# lte.net
KiCad netlist of a schematic drawn in Altium Designer
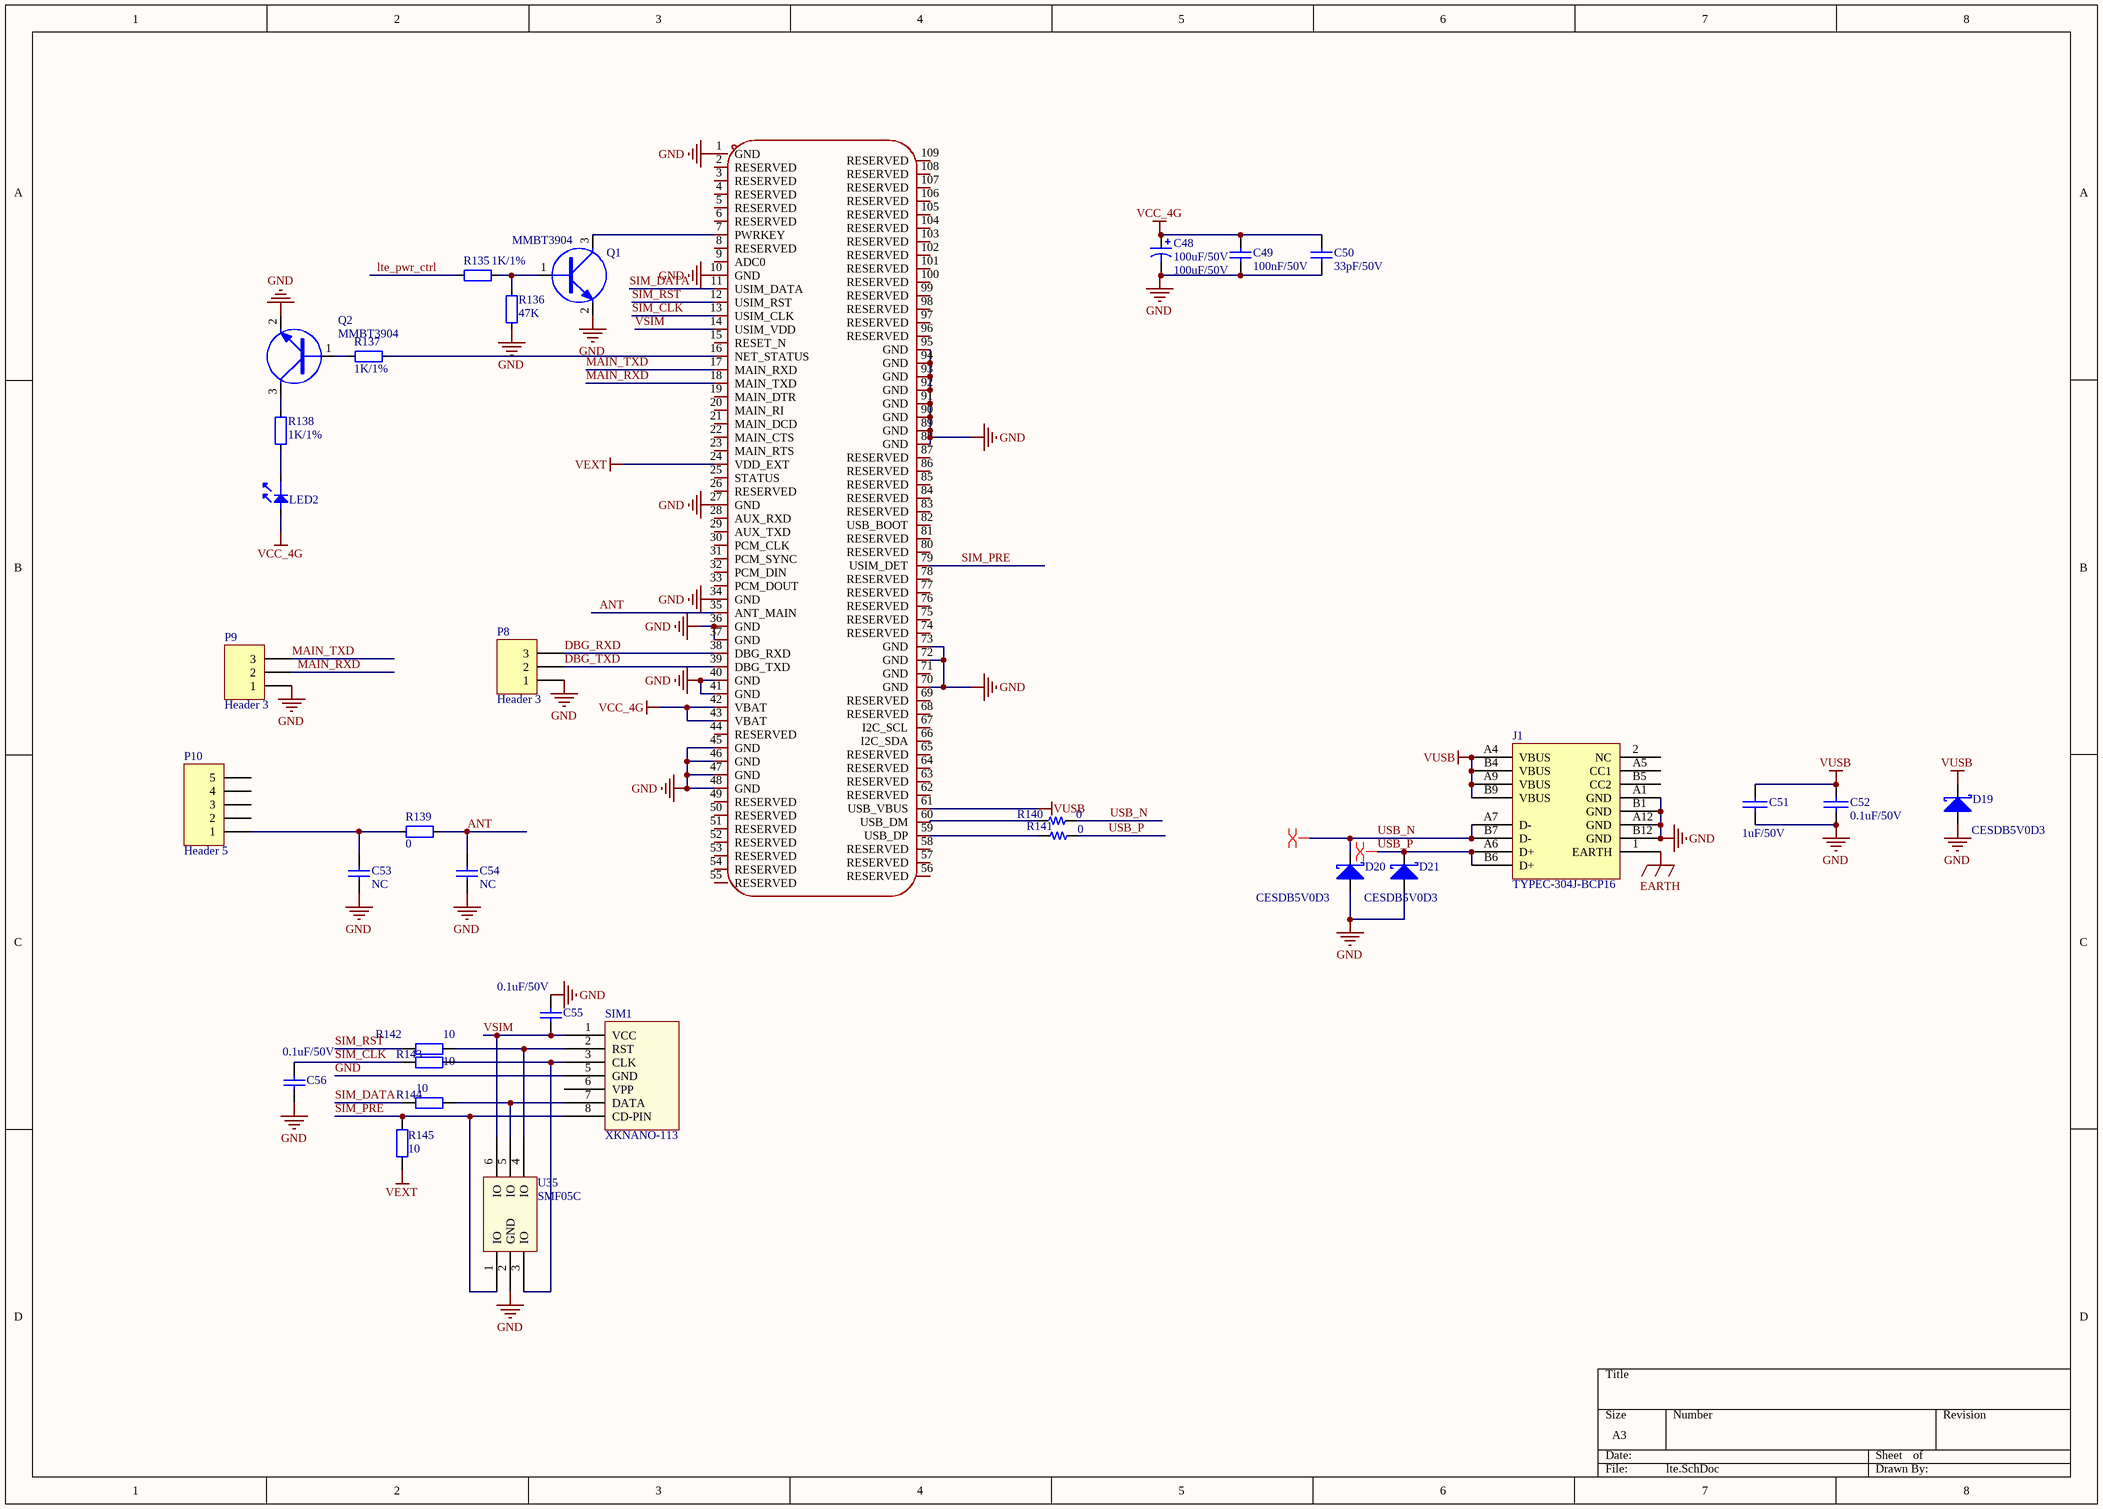
[diagram p0: lte.SchDoc]

(export (version "E")
  (design (tool "Eeschema 10.0.6"))
  (components
    (comp (ref "C48")
      (value "100uF/50V")
      (footprint "CAP-SMD_BD6.3-L6.5-W6.5-LS7.0-FD:CAP-SMD_BD6.3-L6.5-W6.5-LS7.0-FD")
      (description "Polarized Capacitor (Surface Mount)")
      (fields (field (name "ALTIUM_VALUE") "100uF/50V"))
      (libsource (lib "Miscellaneous Devices") (part "Cap Pol3"))
    )
    (comp (ref "C49")
      (value "100nF/50V")
      (footprint "0603C")
      (description "Capacitor")
      (libsource (lib "Miscellaneous Devices") (part "Cap"))
    )
    (comp (ref "C50")
      (value "33pF/50V")
      (footprint "0603C")
      (description "Capacitor")
      (libsource (lib "Miscellaneous Devices") (part "Cap"))
    )
    (comp (ref "C51")
      (value "1uF/50V")
      (footprint "CAPC1608X092N_0603")
      (fields (field (name "PARTNUMBER") "CL10A105KB8NNNC"))
      (libsource (lib "SM") (part "CAP"))
    )
    (comp (ref "C52")
      (value "0.1uF/50V")
      (footprint "CAPC1608X092N_0603")
      (fields (field (name "PARTNUMBER") "CC0603KRX7R9BB104"))
      (libsource (lib "SM") (part "CAP"))
    )
    (comp (ref "C53")
      (value "NC")
      (footprint "0603c")
      (description "Capacitor")
      (libsource (lib "Miscellaneous Devices") (part "Cap"))
    )
    (comp (ref "C54")
      (value "NC")
      (footprint "0603c")
      (description "Capacitor")
      (libsource (lib "Miscellaneous Devices") (part "Cap"))
    )
    (comp (ref "C55")
      (value "0.1uF/50V")
      (footprint "0603c")
      (description "Capacitor")
      (libsource (lib "Miscellaneous Devices") (part "Cap"))
    )
    (comp (ref "C56")
      (value "0.1uF/50V")
      (footprint "0603c")
      (description "Capacitor")
      (libsource (lib "Miscellaneous Devices") (part "Cap"))
    )
    (comp (ref "D19") (value "CESDB5V0D3") (footprint "SOD323") (libsource (lib "*") (part "DIODE S")))
    (comp (ref "D20") (value "CESDB5V0D3") (footprint "SOD323") (libsource (lib "*") (part "DIODE S")))
    (comp (ref "D21") (value "CESDB5V0D3") (footprint "SOD323") (libsource (lib "*") (part "DIODE S")))
    (comp (ref "J1")
      (value "TYPEC-304J-BCP16")
      (footprint "TYPEC_16P")
      (libsource (lib "Schlib_20110825") (part "TYPE C_16P"))
    )
    (comp (ref "LED2")
      (value "LED_Green_19-217")
      (footprint "0603led")
      (libsource (lib "RC_M_D_00") (part "LED_Green_19-217"))
    )
    (comp (ref "P8")
      (value "Header 3")
      (footprint "HDR1X3")
      (description "Header, 3-Pin")
      (libsource (lib "Miscellaneous Connectors") (part "Header 3"))
    )
    (comp (ref "P9")
      (value "Header 3")
      (footprint "HDR1X3")
      (description "Header, 3-Pin")
      (libsource (lib "Miscellaneous Connectors") (part "Header 3"))
    )
    (comp (ref "P10")
      (value "Header 5")
      (footprint "controller_V1.3.1:KH-SMA-KE-Z")
      (description "Header, 5-Pin")
      (libsource (lib "Miscellaneous Connectors") (part "Header 5"))
    )
    (comp (ref "Q1")
      (value "MMBT3904")
      (footprint "SOT23-3")
      (libsource (lib "CenLib") (part "NPN_MMBT3904"))
    )
    (comp (ref "Q2")
      (value "MMBT3904")
      (footprint "SOT23-3")
      (libsource (lib "CenLib") (part "NPN_MMBT3904"))
    )
    (comp (ref "R135") (value "1K/1%") (footprint "0603R") (libsource (lib "RC_M_D_00") (part "RES0603")))
    (comp (ref "R136") (value "47K") (footprint "0603r") (libsource (lib "RC_M_D_00") (part "RES0603")))
    (comp (ref "R137") (value "1K/1%") (footprint "0603r") (libsource (lib "RC_M_D_00") (part "RES0603")))
    (comp (ref "R138") (value "1K/1%") (footprint "0603R") (libsource (lib "RC_M_D_00") (part "RES0603")))
    (comp (ref "R139") (value "0") (footprint "0603r") (libsource (lib "RC_M_D_00") (part "RES0603")))
    (comp (ref "R140")
      (value "0")
      (footprint "RESC1608X055N_0603")
      (fields (field (name "PARTNUMBER") "RC0603FR-071KL"))
      (libsource (lib "JRJ_1") (part "R"))
    )
    (comp (ref "R141")
      (value "0")
      (footprint "RESC1608X055N_0603")
      (fields (field (name "PARTNUMBER") "RC0603FR-071KL"))
      (libsource (lib "JRJ_1") (part "R"))
    )
    (comp (ref "R142")
      (value "10")
      (footprint "0603r")
      (description "Resistor")
      (libsource (lib "Miscellaneous Devices") (part "Res2"))
    )
    (comp (ref "R143")
      (value "10")
      (footprint "0603r")
      (description "Resistor")
      (libsource (lib "Miscellaneous Devices") (part "Res2"))
    )
    (comp (ref "R144")
      (value "10")
      (footprint "0603r")
      (description "Resistor")
      (libsource (lib "Miscellaneous Devices") (part "Res2"))
    )
    (comp (ref "R145")
      (value "10")
      (footprint "0603r")
      (description "Resistor")
      (libsource (lib "") (part "Res2_1"))
    )
    (comp (ref "SIM1") (value "XKNANO-113") (footprint "Nano SIM") (libsource (lib "lm") (part "nano sim")))
    (comp (ref "U34")
      (value "EC800ECNNQ-N03-SNNSA")
      (footprint "LCC-LGA-109_L17.7-W15.8-P1.10_MC661:LCC-LGA-109_L17.7-W15.8-P1.10_MC661")
      (libsource (lib "altium-import") (part "root_0_EC800ECNNQ-N03-SNNSA_"))
    )
    (comp (ref "U35") (value "SMF05C") (footprint "sc70-6l") (libsource (lib "lm") (part "SMF05C")))
  )
  (nets
    (net (code "1") (name "/ANT") (class "Default")
      (node (ref "C54") (pin "1") (pinfunction "1_1") (pintype "passive"))
      (node (ref "R139") (pin "1") (pinfunction "1_1") (pintype "passive"))
      (node (ref "U34") (pin "35") (pinfunction "ANT_MAIN_35") (pintype "passive"))
    )
    (net (code "2") (name "/DBG_RXD") (class "Default")
      (node (ref "P8") (pin "3") (pinfunction "3_3") (pintype "passive"))
      (node (ref "U34") (pin "38") (pinfunction "DBG_RXD_38") (pintype "passive"))
    )
    (net (code "3") (name "/DBG_TXD") (class "Default")
      (node (ref "P8") (pin "2") (pinfunction "2_2") (pintype "passive"))
      (node (ref "U34") (pin "39") (pinfunction "DBG_TXD_39") (pintype "passive"))
    )
    (net (code "4") (name "/MAIN_RXD") (class "Default")
      (node (ref "P9") (pin "2") (pinfunction "2_2") (pintype "passive"))
      (node (ref "U34") (pin "18") (pinfunction "MAIN_TXD_18") (pintype "passive"))
    )
    (net (code "5") (name "/MAIN_TXD") (class "Default")
      (node (ref "P9") (pin "3") (pinfunction "3_3") (pintype "passive"))
      (node (ref "U34") (pin "17") (pinfunction "MAIN_RXD_17") (pintype "passive"))
    )
    (net (code "6") (name "/SIM_CLK") (class "Default")
      (node (ref "C56") (pin "1") (pinfunction "1_1") (pintype "passive"))
      (node (ref "R143") (pin "2") (pinfunction "2_2") (pintype "passive"))
      (node (ref "U34") (pin "13") (pinfunction "USIM_CLK_13") (pintype "passive"))
    )
    (net (code "7") (name "/SIM_DATA") (class "Default")
      (node (ref "R144") (pin "2") (pinfunction "2_2") (pintype "passive"))
      (node (ref "U34") (pin "11") (pinfunction "USIM_DATA_11") (pintype "passive"))
    )
    (net (code "8") (name "/SIM_PRE") (class "Default")
      (node (ref "R145") (pin "1") (pinfunction "1_1") (pintype "passive"))
      (node (ref "SIM1") (pin "8") (pinfunction "CD-PIN_8") (pintype "passive"))
      (node (ref "U34") (pin "79") (pinfunction "USIM_DET_79") (pintype "passive"))
      (node (ref "U35") (pin "1") (pinfunction "IO_1") (pintype "passive"))
    )
    (net (code "9") (name "/SIM_RST") (class "Default")
      (node (ref "R142") (pin "2") (pinfunction "2_2") (pintype "passive"))
      (node (ref "U34") (pin "12") (pinfunction "USIM_RST_12") (pintype "passive"))
    )
    (net (code "10") (name "/USB_N") (class "Default")
      (node (ref "D20") (pin "2") (pinfunction "K_2") (pintype "passive"))
      (node (ref "J1") (pin "A7") (pinfunction "D-_A7") (pintype "passive"))
      (node (ref "J1") (pin "B7") (pinfunction "D-_B7") (pintype "passive"))
      (node (ref "R140") (pin "1") (pintype "passive"))
    )
    (net (code "11") (name "/USB_P") (class "Default")
      (node (ref "D21") (pin "2") (pinfunction "K_2") (pintype "passive"))
      (node (ref "J1") (pin "A6") (pinfunction "D+_A6") (pintype "passive"))
      (node (ref "J1") (pin "B6") (pinfunction "D+_B6") (pintype "passive"))
      (node (ref "R141") (pin "1") (pintype "passive"))
    )
    (net (code "12") (name "/VSIM") (class "Default")
      (node (ref "C55") (pin "2") (pinfunction "2_2") (pintype "passive"))
      (node (ref "SIM1") (pin "1") (pinfunction "VCC_1") (pintype "passive"))
      (node (ref "U34") (pin "14") (pinfunction "USIM_VDD_14") (pintype "passive"))
      (node (ref "U35") (pin "6") (pinfunction "IO_6") (pintype "passive"))
    )
    (net (code "13") (name "/lte_pwr_ctrl") (class "Default")
      (node (ref "R135") (pin "1") (pinfunction "1_1") (pintype "passive"))
    )
    (net (code "14") (name "EARTH") (class "Default")
      (node (ref "J1") (pin "1") (pinfunction "EARTH_1") (pintype "passive"))
    )
    (net (code "15") (name "GND") (class "Default")
      (node (ref "C48") (pin "2") (pinfunction "2_2") (pintype "passive"))
      (node (ref "C49") (pin "1") (pinfunction "1_1") (pintype "passive"))
      (node (ref "C50") (pin "1") (pinfunction "1_1") (pintype "passive"))
      (node (ref "C51") (pin "1") (pinfunction "1_1") (pintype "passive"))
      (node (ref "C52") (pin "1") (pinfunction "1_1") (pintype "passive"))
      (node (ref "C53") (pin "2") (pinfunction "2_2") (pintype "passive"))
      (node (ref "C54") (pin "2") (pinfunction "2_2") (pintype "passive"))
      (node (ref "C55") (pin "1") (pinfunction "1_1") (pintype "passive"))
      (node (ref "C56") (pin "2") (pinfunction "2_2") (pintype "passive"))
      (node (ref "D19") (pin "1") (pinfunction "A_1") (pintype "passive"))
      (node (ref "D20") (pin "1") (pinfunction "A_1") (pintype "passive"))
      (node (ref "D21") (pin "1") (pinfunction "A_1") (pintype "passive"))
      (node (ref "J1") (pin "A1") (pinfunction "GND_A1") (pintype "passive"))
      (node (ref "J1") (pin "A12") (pinfunction "GND_A12") (pintype "passive"))
      (node (ref "J1") (pin "B1") (pinfunction "GND_B1") (pintype "passive"))
      (node (ref "J1") (pin "B12") (pinfunction "GND_B12") (pintype "passive"))
      (node (ref "P8") (pin "1") (pinfunction "1_1") (pintype "passive"))
      (node (ref "P9") (pin "1") (pinfunction "1_1") (pintype "passive"))
      (node (ref "Q1") (pin "2") (pinfunction "E_2") (pintype "passive"))
      (node (ref "Q2") (pin "2") (pinfunction "E_2") (pintype "passive"))
      (node (ref "R136") (pin "1") (pinfunction "1_1") (pintype "passive"))
      (node (ref "SIM1") (pin "5") (pinfunction "GND_5") (pintype "passive"))
      (node (ref "U34") (pin "1") (pinfunction "GND_1") (pintype "passive"))
      (node (ref "U34") (pin "10") (pinfunction "GND_10") (pintype "passive"))
      (node (ref "U34") (pin "27") (pinfunction "GND_27") (pintype "passive"))
      (node (ref "U34") (pin "34") (pinfunction "GND_34") (pintype "passive"))
      (node (ref "U34") (pin "36") (pinfunction "GND_36") (pintype "passive"))
      (node (ref "U34") (pin "37") (pinfunction "GND_37") (pintype "passive"))
      (node (ref "U34") (pin "40") (pinfunction "GND_40") (pintype "passive"))
      (node (ref "U34") (pin "41") (pinfunction "GND_41") (pintype "passive"))
      (node (ref "U34") (pin "45") (pinfunction "GND_45") (pintype "passive"))
      (node (ref "U34") (pin "46") (pinfunction "GND_46") (pintype "passive"))
      (node (ref "U34") (pin "47") (pinfunction "GND_47") (pintype "passive"))
      (node (ref "U34") (pin "48") (pinfunction "GND_48") (pintype "passive"))
      (node (ref "U34") (pin "70") (pinfunction "GND_70") (pintype "passive"))
      (node (ref "U34") (pin "72") (pinfunction "GND_72") (pintype "passive"))
      (node (ref "U34") (pin "73") (pinfunction "GND_73") (pintype "passive"))
      (node (ref "U34") (pin "88") (pinfunction "GND_88") (pintype "passive"))
      (node (ref "U34") (pin "89") (pinfunction "GND_89") (pintype "passive"))
      (node (ref "U34") (pin "90") (pinfunction "GND_90") (pintype "passive"))
      (node (ref "U34") (pin "91") (pinfunction "GND_91") (pintype "passive"))
      (node (ref "U34") (pin "92") (pinfunction "GND_92") (pintype "passive"))
      (node (ref "U34") (pin "93") (pinfunction "GND_93") (pintype "passive"))
      (node (ref "U34") (pin "94") (pinfunction "GND_94") (pintype "passive"))
      (node (ref "U34") (pin "95") (pinfunction "GND_95") (pintype "passive"))
      (node (ref "U35") (pin "2") (pinfunction "GND_2") (pintype "passive"))
    )
    (net (code "16") (name "Net-(C53-Pad1)") (class "Default")
      (node (ref "C53") (pin "1") (pinfunction "1_1") (pintype "passive"))
      (node (ref "P10") (pin "1") (pinfunction "1_1") (pintype "passive"))
      (node (ref "R139") (pin "2") (pinfunction "2_2") (pintype "passive"))
    )
    (net (code "17") (name "Net-(LED2-Pad2)") (class "Default")
      (node (ref "LED2") (pin "2") (pinfunction "2_2") (pintype "passive"))
      (node (ref "R138") (pin "1") (pinfunction "1_1") (pintype "passive"))
    )
    (net (code "18") (name "Net-(Q1-B)") (class "Default")
      (node (ref "Q1") (pin "1") (pinfunction "B_1") (pintype "passive"))
      (node (ref "R135") (pin "2") (pinfunction "2_2") (pintype "passive"))
      (node (ref "R136") (pin "2") (pinfunction "2_2") (pintype "passive"))
    )
    (net (code "19") (name "Net-(Q1-C)") (class "Default")
      (node (ref "Q1") (pin "3") (pinfunction "C_3") (pintype "passive"))
      (node (ref "U34") (pin "7") (pinfunction "PWRKEY_7") (pintype "passive"))
    )
    (net (code "20") (name "Net-(Q2-B)") (class "Default")
      (node (ref "Q2") (pin "1") (pinfunction "B_1") (pintype "passive"))
      (node (ref "R137") (pin "2") (pinfunction "2_2") (pintype "passive"))
    )
    (net (code "21") (name "Net-(Q2-C)") (class "Default")
      (node (ref "Q2") (pin "3") (pinfunction "C_3") (pintype "passive"))
      (node (ref "R138") (pin "2") (pinfunction "2_2") (pintype "passive"))
    )
    (net (code "22") (name "Net-(SIM1-CLK)") (class "Default")
      (node (ref "R143") (pin "1") (pinfunction "1_1") (pintype "passive"))
      (node (ref "SIM1") (pin "3") (pinfunction "CLK_3") (pintype "passive"))
      (node (ref "U35") (pin "3") (pinfunction "IO_3") (pintype "passive"))
    )
    (net (code "23") (name "Net-(SIM1-DATA)") (class "Default")
      (node (ref "R144") (pin "1") (pinfunction "1_1") (pintype "passive"))
      (node (ref "SIM1") (pin "7") (pinfunction "DATA_7") (pintype "passive"))
      (node (ref "U35") (pin "5") (pinfunction "IO_5") (pintype "passive"))
    )
    (net (code "24") (name "Net-(SIM1-RST)") (class "Default")
      (node (ref "R142") (pin "1") (pinfunction "1_1") (pintype "passive"))
      (node (ref "SIM1") (pin "2") (pinfunction "RST_2") (pintype "passive"))
      (node (ref "U35") (pin "4") (pinfunction "IO_4") (pintype "passive"))
    )
    (net (code "25") (name "Net-(U34-NET_STATUS)") (class "Default")
      (node (ref "R137") (pin "1") (pinfunction "1_1") (pintype "passive"))
      (node (ref "U34") (pin "16") (pinfunction "NET_STATUS_16") (pintype "passive"))
    )
    (net (code "26") (name "Net-(U34-USB_DM)") (class "Default")
      (node (ref "R140") (pin "2") (pintype "passive"))
      (node (ref "U34") (pin "60") (pinfunction "USB_DM_60") (pintype "passive"))
    )
    (net (code "27") (name "Net-(U34-USB_DP)") (class "Default")
      (node (ref "R141") (pin "2") (pintype "passive"))
      (node (ref "U34") (pin "59") (pinfunction "USB_DP_59") (pintype "passive"))
    )
    (net (code "28") (name "VCC_4G") (class "Default")
      (node (ref "C48") (pin "1") (pinfunction "1_1") (pintype "passive"))
      (node (ref "C49") (pin "2") (pinfunction "2_2") (pintype "passive"))
      (node (ref "C50") (pin "2") (pinfunction "2_2") (pintype "passive"))
      (node (ref "LED2") (pin "1") (pinfunction "1_1") (pintype "passive"))
      (node (ref "U34") (pin "42") (pinfunction "VBAT_42") (pintype "passive"))
      (node (ref "U34") (pin "43") (pinfunction "VBAT_43") (pintype "passive"))
    )
    (net (code "29") (name "VEXT") (class "Default")
      (node (ref "R145") (pin "2") (pinfunction "2_2") (pintype "passive"))
      (node (ref "U34") (pin "24") (pinfunction "VDD_EXT_24") (pintype "passive"))
    )
    (net (code "30") (name "VUSB") (class "Default")
      (node (ref "C51") (pin "2") (pinfunction "2_2") (pintype "passive"))
      (node (ref "C52") (pin "2") (pinfunction "2_2") (pintype "passive"))
      (node (ref "D19") (pin "2") (pinfunction "K_2") (pintype "passive"))
      (node (ref "J1") (pin "A4") (pinfunction "VBUS_A4") (pintype "passive"))
      (node (ref "J1") (pin "A9") (pinfunction "VBUS_A9") (pintype "passive"))
      (node (ref "J1") (pin "B4") (pinfunction "VBUS_B4") (pintype "passive"))
      (node (ref "J1") (pin "B9") (pinfunction "VBUS_B9") (pintype "passive"))
      (node (ref "U34") (pin "61") (pinfunction "USB_VBUS_61") (pintype "passive"))
    )
    (net (code "31") (name "unconnected-(J1-CC1-PadA5)") (class "Default")
      (node (ref "J1") (pin "A5") (pinfunction "CC1_A5") (pintype "passive"))
    )
    (net (code "32") (name "unconnected-(J1-CC2-PadB5)") (class "Default")
      (node (ref "J1") (pin "B5") (pinfunction "CC2_B5") (pintype "passive"))
    )
    (net (code "33") (name "unconnected-(J1-NC-Pad2)") (class "Default")
      (node (ref "J1") (pin "2") (pinfunction "NC_2") (pintype "passive"))
    )
    (net (code "34") (name "unconnected-(P10-Pad2)") (class "Default")
      (node (ref "P10") (pin "2") (pinfunction "2_2") (pintype "passive"))
    )
    (net (code "35") (name "unconnected-(P10-Pad3)") (class "Default")
      (node (ref "P10") (pin "3") (pinfunction "3_3") (pintype "passive"))
    )
    (net (code "36") (name "unconnected-(P10-Pad4)") (class "Default")
      (node (ref "P10") (pin "4") (pinfunction "4_4") (pintype "passive"))
    )
    (net (code "37") (name "unconnected-(P10-Pad5)") (class "Default")
      (node (ref "P10") (pin "5") (pinfunction "5_5") (pintype "passive"))
    )
    (net (code "38") (name "unconnected-(SIM1-VPP-Pad6)") (class "Default")
      (node (ref "SIM1") (pin "6") (pinfunction "VPP_6") (pintype "passive"))
    )
    (net (code "39") (name "unconnected-(U34-ADC0-Pad9)") (class "Default")
      (node (ref "U34") (pin "9") (pinfunction "ADC0_9") (pintype "passive"))
    )
    (net (code "40") (name "unconnected-(U34-AUX_RXD-Pad28)") (class "Default")
      (node (ref "U34") (pin "28") (pinfunction "AUX_RXD_28") (pintype "passive"))
    )
    (net (code "41") (name "unconnected-(U34-AUX_TXD-Pad29)") (class "Default")
      (node (ref "U34") (pin "29") (pinfunction "AUX_TXD_29") (pintype "passive"))
    )
    (net (code "42") (name "unconnected-(U34-GND-Pad71)") (class "Default")
      (node (ref "U34") (pin "71") (pinfunction "GND_71") (pintype "passive"))
    )
    (net (code "43") (name "unconnected-(U34-I2C_SCL-Pad67)") (class "Default")
      (node (ref "U34") (pin "67") (pinfunction "I2C_SCL_67") (pintype "passive"))
    )
    (net (code "44") (name "unconnected-(U34-I2C_SDA-Pad66)") (class "Default")
      (node (ref "U34") (pin "66") (pinfunction "I2C_SDA_66") (pintype "passive"))
    )
    (net (code "45") (name "unconnected-(U34-MAIN_CTS-Pad22)") (class "Default")
      (node (ref "U34") (pin "22") (pinfunction "MAIN_CTS_22") (pintype "passive"))
    )
    (net (code "46") (name "unconnected-(U34-MAIN_DCD-Pad21)") (class "Default")
      (node (ref "U34") (pin "21") (pinfunction "MAIN_DCD_21") (pintype "passive"))
    )
    (net (code "47") (name "unconnected-(U34-MAIN_DTR-Pad19)") (class "Default")
      (node (ref "U34") (pin "19") (pinfunction "MAIN_DTR_19") (pintype "passive"))
    )
    (net (code "48") (name "unconnected-(U34-MAIN_RI-Pad20)") (class "Default")
      (node (ref "U34") (pin "20") (pinfunction "MAIN_RI_20") (pintype "passive"))
    )
    (net (code "49") (name "unconnected-(U34-MAIN_RTS-Pad23)") (class "Default")
      (node (ref "U34") (pin "23") (pinfunction "MAIN_RTS_23") (pintype "passive"))
    )
    (net (code "50") (name "unconnected-(U34-PCM_CLK-Pad30)") (class "Default")
      (node (ref "U34") (pin "30") (pinfunction "PCM_CLK_30") (pintype "passive"))
    )
    (net (code "51") (name "unconnected-(U34-PCM_DIN-Pad32)") (class "Default")
      (node (ref "U34") (pin "32") (pinfunction "PCM_DIN_32") (pintype "passive"))
    )
    (net (code "52") (name "unconnected-(U34-PCM_DOUT-Pad33)") (class "Default")
      (node (ref "U34") (pin "33") (pinfunction "PCM_DOUT_33") (pintype "passive"))
    )
    (net (code "53") (name "unconnected-(U34-PCM_SYNC-Pad31)") (class "Default")
      (node (ref "U34") (pin "31") (pinfunction "PCM_SYNC_31") (pintype "passive"))
    )
    (net (code "54") (name "unconnected-(U34-RESERVED-Pad2)") (class "Default")
      (node (ref "U34") (pin "2") (pinfunction "RESERVED_2") (pintype "passive"))
    )
    (net (code "55") (name "unconnected-(U34-RESERVED-Pad3)") (class "Default")
      (node (ref "U34") (pin "3") (pinfunction "RESERVED_3") (pintype "passive"))
    )
    (net (code "56") (name "unconnected-(U34-RESERVED-Pad4)") (class "Default")
      (node (ref "U34") (pin "4") (pinfunction "RESERVED_4") (pintype "passive"))
    )
    (net (code "57") (name "unconnected-(U34-RESERVED-Pad5)") (class "Default")
      (node (ref "U34") (pin "5") (pinfunction "RESERVED_5") (pintype "passive"))
    )
    (net (code "58") (name "unconnected-(U34-RESERVED-Pad6)") (class "Default")
      (node (ref "U34") (pin "6") (pinfunction "RESERVED_6") (pintype "passive"))
    )
    (net (code "59") (name "unconnected-(U34-RESERVED-Pad8)") (class "Default")
      (node (ref "U34") (pin "8") (pinfunction "RESERVED_8") (pintype "passive"))
    )
    (net (code "60") (name "unconnected-(U34-RESERVED-Pad26)") (class "Default")
      (node (ref "U34") (pin "26") (pinfunction "RESERVED_26") (pintype "passive"))
    )
    (net (code "61") (name "unconnected-(U34-RESERVED-Pad44)") (class "Default")
      (node (ref "U34") (pin "44") (pinfunction "RESERVED_44") (pintype "passive"))
    )
    (net (code "62") (name "unconnected-(U34-RESERVED-Pad49)") (class "Default")
      (node (ref "U34") (pin "49") (pinfunction "RESERVED_49") (pintype "passive"))
    )
    (net (code "63") (name "unconnected-(U34-RESERVED-Pad50)") (class "Default")
      (node (ref "U34") (pin "50") (pinfunction "RESERVED_50") (pintype "passive"))
    )
    (net (code "64") (name "unconnected-(U34-RESERVED-Pad51)") (class "Default")
      (node (ref "U34") (pin "51") (pinfunction "RESERVED_51") (pintype "passive"))
    )
    (net (code "65") (name "unconnected-(U34-RESERVED-Pad52)") (class "Default")
      (node (ref "U34") (pin "52") (pinfunction "RESERVED_52") (pintype "passive"))
    )
    (net (code "66") (name "unconnected-(U34-RESERVED-Pad53)") (class "Default")
      (node (ref "U34") (pin "53") (pinfunction "RESERVED_53") (pintype "passive"))
    )
    (net (code "67") (name "unconnected-(U34-RESERVED-Pad54)") (class "Default")
      (node (ref "U34") (pin "54") (pinfunction "RESERVED_54") (pintype "passive"))
    )
    (net (code "68") (name "unconnected-(U34-RESERVED-Pad55)") (class "Default")
      (node (ref "U34") (pin "55") (pinfunction "RESERVED_55") (pintype "passive"))
    )
    (net (code "69") (name "unconnected-(U34-RESERVED-Pad56)") (class "Default")
      (node (ref "U34") (pin "56") (pinfunction "RESERVED_56") (pintype "passive"))
    )
    (net (code "70") (name "unconnected-(U34-RESERVED-Pad57)") (class "Default")
      (node (ref "U34") (pin "57") (pinfunction "RESERVED_57") (pintype "passive"))
    )
    (net (code "71") (name "unconnected-(U34-RESERVED-Pad58)") (class "Default")
      (node (ref "U34") (pin "58") (pinfunction "RESERVED_58") (pintype "passive"))
    )
    (net (code "72") (name "unconnected-(U34-RESERVED-Pad62)") (class "Default")
      (node (ref "U34") (pin "62") (pinfunction "RESERVED_62") (pintype "passive"))
    )
    (net (code "73") (name "unconnected-(U34-RESERVED-Pad63)") (class "Default")
      (node (ref "U34") (pin "63") (pinfunction "RESERVED_63") (pintype "passive"))
    )
    (net (code "74") (name "unconnected-(U34-RESERVED-Pad64)") (class "Default")
      (node (ref "U34") (pin "64") (pinfunction "RESERVED_64") (pintype "passive"))
    )
    (net (code "75") (name "unconnected-(U34-RESERVED-Pad65)") (class "Default")
      (node (ref "U34") (pin "65") (pinfunction "RESERVED_65") (pintype "passive"))
    )
    (net (code "76") (name "unconnected-(U34-RESERVED-Pad68)") (class "Default")
      (node (ref "U34") (pin "68") (pinfunction "RESERVED_68") (pintype "passive"))
    )
    (net (code "77") (name "unconnected-(U34-RESERVED-Pad69)") (class "Default")
      (node (ref "U34") (pin "69") (pinfunction "RESERVED_69") (pintype "passive"))
    )
    (net (code "78") (name "unconnected-(U34-RESERVED-Pad74)") (class "Default")
      (node (ref "U34") (pin "74") (pinfunction "RESERVED_74") (pintype "passive"))
    )
    (net (code "79") (name "unconnected-(U34-RESERVED-Pad75)") (class "Default")
      (node (ref "U34") (pin "75") (pinfunction "RESERVED_75") (pintype "passive"))
    )
    (net (code "80") (name "unconnected-(U34-RESERVED-Pad76)") (class "Default")
      (node (ref "U34") (pin "76") (pinfunction "RESERVED_76") (pintype "passive"))
    )
    (net (code "81") (name "unconnected-(U34-RESERVED-Pad77)") (class "Default")
      (node (ref "U34") (pin "77") (pinfunction "RESERVED_77") (pintype "passive"))
    )
    (net (code "82") (name "unconnected-(U34-RESERVED-Pad78)") (class "Default")
      (node (ref "U34") (pin "78") (pinfunction "RESERVED_78") (pintype "passive"))
    )
    (net (code "83") (name "unconnected-(U34-RESERVED-Pad80)") (class "Default")
      (node (ref "U34") (pin "80") (pinfunction "RESERVED_80") (pintype "passive"))
    )
    (net (code "84") (name "unconnected-(U34-RESERVED-Pad81)") (class "Default")
      (node (ref "U34") (pin "81") (pinfunction "RESERVED_81") (pintype "passive"))
    )
    (net (code "85") (name "unconnected-(U34-RESERVED-Pad83)") (class "Default")
      (node (ref "U34") (pin "83") (pinfunction "RESERVED_83") (pintype "passive"))
    )
    (net (code "86") (name "unconnected-(U34-RESERVED-Pad84)") (class "Default")
      (node (ref "U34") (pin "84") (pinfunction "RESERVED_84") (pintype "passive"))
    )
    (net (code "87") (name "unconnected-(U34-RESERVED-Pad85)") (class "Default")
      (node (ref "U34") (pin "85") (pinfunction "RESERVED_85") (pintype "passive"))
    )
    (net (code "88") (name "unconnected-(U34-RESERVED-Pad86)") (class "Default")
      (node (ref "U34") (pin "86") (pinfunction "RESERVED_86") (pintype "passive"))
    )
    (net (code "89") (name "unconnected-(U34-RESERVED-Pad87)") (class "Default")
      (node (ref "U34") (pin "87") (pinfunction "RESERVED_87") (pintype "passive"))
    )
    (net (code "90") (name "unconnected-(U34-RESERVED-Pad96)") (class "Default")
      (node (ref "U34") (pin "96") (pinfunction "RESERVED_96") (pintype "passive"))
    )
    (net (code "91") (name "unconnected-(U34-RESERVED-Pad97)") (class "Default")
      (node (ref "U34") (pin "97") (pinfunction "RESERVED_97") (pintype "passive"))
    )
    (net (code "92") (name "unconnected-(U34-RESERVED-Pad98)") (class "Default")
      (node (ref "U34") (pin "98") (pinfunction "RESERVED_98") (pintype "passive"))
    )
    (net (code "93") (name "unconnected-(U34-RESERVED-Pad99)") (class "Default")
      (node (ref "U34") (pin "99") (pinfunction "RESERVED_99") (pintype "passive"))
    )
    (net (code "94") (name "unconnected-(U34-RESERVED-Pad100)") (class "Default")
      (node (ref "U34") (pin "100") (pinfunction "RESERVED_100") (pintype "passive"))
    )
    (net (code "95") (name "unconnected-(U34-RESERVED-Pad101)") (class "Default")
      (node (ref "U34") (pin "101") (pinfunction "RESERVED_101") (pintype "passive"))
    )
    (net (code "96") (name "unconnected-(U34-RESERVED-Pad102)") (class "Default")
      (node (ref "U34") (pin "102") (pinfunction "RESERVED_102") (pintype "passive"))
    )
    (net (code "97") (name "unconnected-(U34-RESERVED-Pad103)") (class "Default")
      (node (ref "U34") (pin "103") (pinfunction "RESERVED_103") (pintype "passive"))
    )
    (net (code "98") (name "unconnected-(U34-RESERVED-Pad104)") (class "Default")
      (node (ref "U34") (pin "104") (pinfunction "RESERVED_104") (pintype "passive"))
    )
    (net (code "99") (name "unconnected-(U34-RESERVED-Pad105)") (class "Default")
      (node (ref "U34") (pin "105") (pinfunction "RESERVED_105") (pintype "passive"))
    )
    (net (code "100") (name "unconnected-(U34-RESERVED-Pad106)") (class "Default")
      (node (ref "U34") (pin "106") (pinfunction "RESERVED_106") (pintype "passive"))
    )
    (net (code "101") (name "unconnected-(U34-RESERVED-Pad107)") (class "Default")
      (node (ref "U34") (pin "107") (pinfunction "RESERVED_107") (pintype "passive"))
    )
    (net (code "102") (name "unconnected-(U34-RESERVED-Pad108)") (class "Default")
      (node (ref "U34") (pin "108") (pinfunction "RESERVED_108") (pintype "passive"))
    )
    (net (code "103") (name "unconnected-(U34-RESERVED-Pad109)") (class "Default")
      (node (ref "U34") (pin "109") (pinfunction "RESERVED_109") (pintype "passive"))
    )
    (net (code "104") (name "unconnected-(U34-RESET_N-Pad15)") (class "Default")
      (node (ref "U34") (pin "15") (pinfunction "RESET_N_15") (pintype "passive"))
    )
    (net (code "105") (name "unconnected-(U34-STATUS-Pad25)") (class "Default")
      (node (ref "U34") (pin "25") (pinfunction "STATUS_25") (pintype "passive"))
    )
    (net (code "106") (name "unconnected-(U34-USB_BOOT-Pad82)") (class "Default")
      (node (ref "U34") (pin "82") (pinfunction "USB_BOOT_82") (pintype "passive"))
    )
  )
)
